# Connectors_and_Headers.net
KiCad netlist of a schematic drawn in Altium Designer
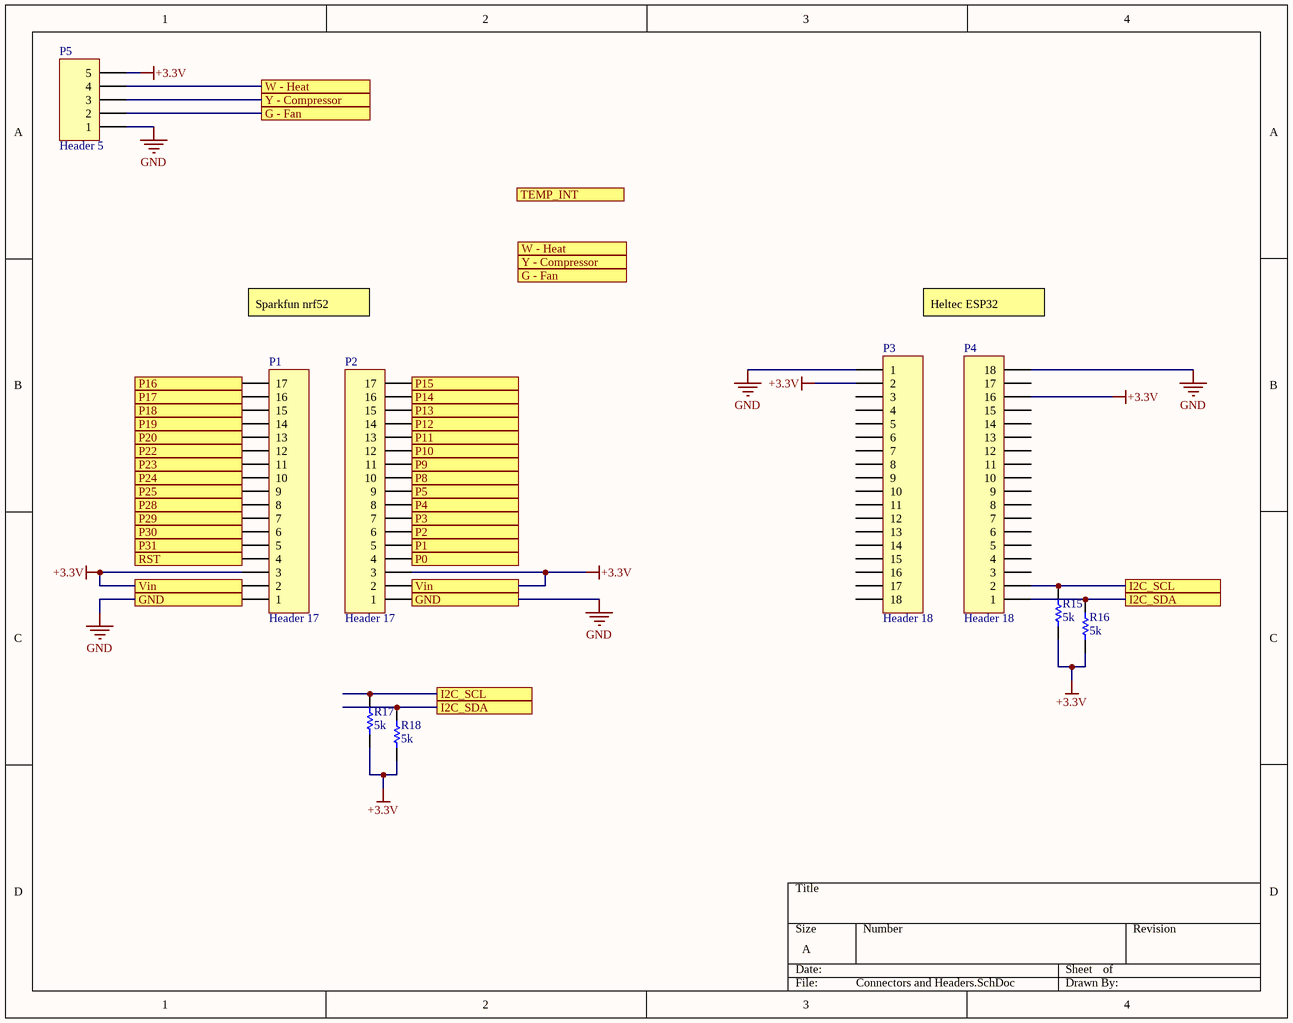
[diagram p0: Connectors and Headers.SchDoc]

(export (version "E")
  (design (tool "Eeschema 10.0.6"))
  (components
    (comp (ref "P1")
      (value "Header 17")
      (footprint "HDR1X17")
      (description "Header, 17-Pin")
      (fields (field (name "PUBLISHER") "Altium Limited"))
      (libsource (lib "Miscellaneous Connectors") (part "Header 17"))
    )
    (comp (ref "P2")
      (value "Header 17")
      (footprint "HDR1X17")
      (description "Header, 17-Pin")
      (fields (field (name "PUBLISHER") "Altium Limited"))
      (libsource (lib "") (part "Header 17_1"))
    )
    (comp (ref "P3")
      (value "Header 18")
      (footprint "HDR1X18")
      (description "Header, 18-Pin")
      (fields (field (name "PUBLISHER") "Altium Limited"))
      (libsource (lib "Miscellaneous Connectors") (part "Header 18"))
    )
    (comp (ref "P4")
      (value "Header 18")
      (footprint "HDR1X18")
      (description "Header, 18-Pin")
      (fields (field (name "PUBLISHER") "Altium Limited"))
      (libsource (lib "") (part "Header 18_1"))
    )
    (comp (ref "P5")
      (value "Header 5")
      (footprint "HDR1X5")
      (description "Header, 5-Pin")
      (fields (field (name "PUBLISHER") "Altium Limited"))
      (libsource (lib "Miscellaneous Connectors") (part "Header 5"))
    )
    (comp (ref "R15")
      (value "5k")
      (footprint "RESC2013X70X40LL20T20")
      (description "2012")
      (fields (field (name "PART NUMBER") "ERJ-6GEYJ471V") (field (name "MANUFACTURER") "Panasonic"))
      (libsource (lib "Altium Content Vault") (part "RES"))
    )
    (comp (ref "R16")
      (value "5k")
      (footprint "RESC2013X70X40LL20T20")
      (description "2012")
      (fields (field (name "PART NUMBER") "ERJ-6GEYJ471V") (field (name "MANUFACTURER") "Panasonic"))
      (libsource (lib "Altium Content Vault") (part "RES"))
    )
    (comp (ref "R17")
      (value "5k")
      (footprint "RESC2013X70X40LL20T20")
      (description "2012")
      (fields (field (name "PART NUMBER") "ERJ-6GEYJ471V") (field (name "MANUFACTURER") "Panasonic"))
      (libsource (lib "Altium Content Vault") (part "RES"))
    )
    (comp (ref "R18")
      (value "5k")
      (footprint "RESC2013X70X40LL20T20")
      (description "2012")
      (fields (field (name "PART NUMBER") "ERJ-6GEYJ471V") (field (name "MANUFACTURER") "Panasonic"))
      (libsource (lib "Altium Content Vault") (part "RES"))
    )
  )
  (nets
    (net (code "1") (name "+3.3V") (class "Default")
      (node (ref "P1") (pin "2") (pinfunction "2_2") (pintype "passive"))
      (node (ref "P1") (pin "3") (pinfunction "3_3") (pintype "passive"))
      (node (ref "P2") (pin "2") (pinfunction "2_2") (pintype "passive"))
      (node (ref "P2") (pin "3") (pinfunction "3_3") (pintype "passive"))
      (node (ref "P3") (pin "2") (pinfunction "2_2") (pintype "passive"))
      (node (ref "P4") (pin "16") (pinfunction "16_16") (pintype "passive"))
      (node (ref "P5") (pin "5") (pinfunction "5_5") (pintype "passive"))
      (node (ref "R15") (pin "1") (pinfunction "1_1") (pintype "passive"))
      (node (ref "R16") (pin "1") (pinfunction "1_1") (pintype "passive"))
      (node (ref "R17") (pin "1") (pinfunction "1_1") (pintype "passive"))
      (node (ref "R18") (pin "1") (pinfunction "1_1") (pintype "passive"))
    )
    (net (code "2") (name "/G - Fan") (class "Default")
      (node (ref "P5") (pin "2") (pinfunction "2_2") (pintype "passive"))
    )
    (net (code "3") (name "/I2C_SCL") (class "Default")
      (node (ref "P4") (pin "2") (pinfunction "2_2") (pintype "passive"))
      (node (ref "R15") (pin "2") (pinfunction "2_2") (pintype "passive"))
      (node (ref "R17") (pin "2") (pinfunction "2_2") (pintype "passive"))
    )
    (net (code "4") (name "/I2C_SDA") (class "Default")
      (node (ref "P4") (pin "1") (pinfunction "1_1") (pintype "passive"))
      (node (ref "R16") (pin "2") (pinfunction "2_2") (pintype "passive"))
      (node (ref "R18") (pin "2") (pinfunction "2_2") (pintype "passive"))
    )
    (net (code "5") (name "/P0") (class "Default")
      (node (ref "P2") (pin "4") (pinfunction "4_4") (pintype "passive"))
    )
    (net (code "6") (name "/P1") (class "Default")
      (node (ref "P2") (pin "5") (pinfunction "5_5") (pintype "passive"))
    )
    (net (code "7") (name "/P2") (class "Default")
      (node (ref "P2") (pin "6") (pinfunction "6_6") (pintype "passive"))
    )
    (net (code "8") (name "/P3") (class "Default")
      (node (ref "P2") (pin "7") (pinfunction "7_7") (pintype "passive"))
    )
    (net (code "9") (name "/P4") (class "Default")
      (node (ref "P2") (pin "8") (pinfunction "8_8") (pintype "passive"))
    )
    (net (code "10") (name "/P5") (class "Default")
      (node (ref "P2") (pin "9") (pinfunction "9_9") (pintype "passive"))
    )
    (net (code "11") (name "/P8") (class "Default")
      (node (ref "P2") (pin "10") (pinfunction "10_10") (pintype "passive"))
    )
    (net (code "12") (name "/P9") (class "Default")
      (node (ref "P2") (pin "11") (pinfunction "11_11") (pintype "passive"))
    )
    (net (code "13") (name "/P10") (class "Default")
      (node (ref "P2") (pin "12") (pinfunction "12_12") (pintype "passive"))
    )
    (net (code "14") (name "/P11") (class "Default")
      (node (ref "P2") (pin "13") (pinfunction "13_13") (pintype "passive"))
    )
    (net (code "15") (name "/P12") (class "Default")
      (node (ref "P2") (pin "14") (pinfunction "14_14") (pintype "passive"))
    )
    (net (code "16") (name "/P13") (class "Default")
      (node (ref "P2") (pin "15") (pinfunction "15_15") (pintype "passive"))
    )
    (net (code "17") (name "/P14") (class "Default")
      (node (ref "P2") (pin "16") (pinfunction "16_16") (pintype "passive"))
    )
    (net (code "18") (name "/P15") (class "Default")
      (node (ref "P2") (pin "17") (pinfunction "17_17") (pintype "passive"))
    )
    (net (code "19") (name "/P16") (class "Default")
      (node (ref "P1") (pin "17") (pinfunction "17_17") (pintype "passive"))
    )
    (net (code "20") (name "/P17") (class "Default")
      (node (ref "P1") (pin "16") (pinfunction "16_16") (pintype "passive"))
    )
    (net (code "21") (name "/P18") (class "Default")
      (node (ref "P1") (pin "15") (pinfunction "15_15") (pintype "passive"))
    )
    (net (code "22") (name "/P19") (class "Default")
      (node (ref "P1") (pin "14") (pinfunction "14_14") (pintype "passive"))
    )
    (net (code "23") (name "/P20") (class "Default")
      (node (ref "P1") (pin "13") (pinfunction "13_13") (pintype "passive"))
    )
    (net (code "24") (name "/P22") (class "Default")
      (node (ref "P1") (pin "12") (pinfunction "12_12") (pintype "passive"))
    )
    (net (code "25") (name "/P23") (class "Default")
      (node (ref "P1") (pin "11") (pinfunction "11_11") (pintype "passive"))
    )
    (net (code "26") (name "/P24") (class "Default")
      (node (ref "P1") (pin "10") (pinfunction "10_10") (pintype "passive"))
    )
    (net (code "27") (name "/P25") (class "Default")
      (node (ref "P1") (pin "9") (pinfunction "9_9") (pintype "passive"))
    )
    (net (code "28") (name "/P28") (class "Default")
      (node (ref "P1") (pin "8") (pinfunction "8_8") (pintype "passive"))
    )
    (net (code "29") (name "/P29") (class "Default")
      (node (ref "P1") (pin "7") (pinfunction "7_7") (pintype "passive"))
    )
    (net (code "30") (name "/P30") (class "Default")
      (node (ref "P1") (pin "6") (pinfunction "6_6") (pintype "passive"))
    )
    (net (code "31") (name "/P31") (class "Default")
      (node (ref "P1") (pin "5") (pinfunction "5_5") (pintype "passive"))
    )
    (net (code "32") (name "/RST") (class "Default")
      (node (ref "P1") (pin "4") (pinfunction "4_4") (pintype "passive"))
    )
    (net (code "34") (name "/W - Heat") (class "Default")
      (node (ref "P5") (pin "4") (pinfunction "4_4") (pintype "passive"))
    )
    (net (code "35") (name "/Y - Compressor") (class "Default")
      (node (ref "P5") (pin "3") (pinfunction "3_3") (pintype "passive"))
    )
    (net (code "36") (name "GND") (class "Default")
      (node (ref "P1") (pin "1") (pinfunction "1_1") (pintype "passive"))
      (node (ref "P2") (pin "1") (pinfunction "1_1") (pintype "passive"))
      (node (ref "P3") (pin "1") (pinfunction "1_1") (pintype "passive"))
      (node (ref "P4") (pin "18") (pinfunction "18_18") (pintype "passive"))
      (node (ref "P5") (pin "1") (pinfunction "1_1") (pintype "passive"))
    )
    (net (code "37") (name "unconnected-(P3-Pad3)") (class "Default")
      (node (ref "P3") (pin "3") (pinfunction "3_3") (pintype "passive"))
    )
    (net (code "38") (name "unconnected-(P3-Pad4)") (class "Default")
      (node (ref "P3") (pin "4") (pinfunction "4_4") (pintype "passive"))
    )
    (net (code "39") (name "unconnected-(P3-Pad5)") (class "Default")
      (node (ref "P3") (pin "5") (pinfunction "5_5") (pintype "passive"))
    )
    (net (code "40") (name "unconnected-(P3-Pad6)") (class "Default")
      (node (ref "P3") (pin "6") (pinfunction "6_6") (pintype "passive"))
    )
    (net (code "41") (name "unconnected-(P3-Pad7)") (class "Default")
      (node (ref "P3") (pin "7") (pinfunction "7_7") (pintype "passive"))
    )
    (net (code "42") (name "unconnected-(P3-Pad8)") (class "Default")
      (node (ref "P3") (pin "8") (pinfunction "8_8") (pintype "passive"))
    )
    (net (code "43") (name "unconnected-(P3-Pad9)") (class "Default")
      (node (ref "P3") (pin "9") (pinfunction "9_9") (pintype "passive"))
    )
    (net (code "44") (name "unconnected-(P3-Pad10)") (class "Default")
      (node (ref "P3") (pin "10") (pinfunction "10_10") (pintype "passive"))
    )
    (net (code "45") (name "unconnected-(P3-Pad11)") (class "Default")
      (node (ref "P3") (pin "11") (pinfunction "11_11") (pintype "passive"))
    )
    (net (code "46") (name "unconnected-(P3-Pad12)") (class "Default")
      (node (ref "P3") (pin "12") (pinfunction "12_12") (pintype "passive"))
    )
    (net (code "47") (name "unconnected-(P3-Pad13)") (class "Default")
      (node (ref "P3") (pin "13") (pinfunction "13_13") (pintype "passive"))
    )
    (net (code "48") (name "unconnected-(P3-Pad14)") (class "Default")
      (node (ref "P3") (pin "14") (pinfunction "14_14") (pintype "passive"))
    )
    (net (code "49") (name "unconnected-(P3-Pad15)") (class "Default")
      (node (ref "P3") (pin "15") (pinfunction "15_15") (pintype "passive"))
    )
    (net (code "50") (name "unconnected-(P3-Pad16)") (class "Default")
      (node (ref "P3") (pin "16") (pinfunction "16_16") (pintype "passive"))
    )
    (net (code "51") (name "unconnected-(P3-Pad17)") (class "Default")
      (node (ref "P3") (pin "17") (pinfunction "17_17") (pintype "passive"))
    )
    (net (code "52") (name "unconnected-(P3-Pad18)") (class "Default")
      (node (ref "P3") (pin "18") (pinfunction "18_18") (pintype "passive"))
    )
    (net (code "53") (name "unconnected-(P4-Pad3)") (class "Default")
      (node (ref "P4") (pin "3") (pinfunction "3_3") (pintype "passive"))
    )
    (net (code "54") (name "unconnected-(P4-Pad4)") (class "Default")
      (node (ref "P4") (pin "4") (pinfunction "4_4") (pintype "passive"))
    )
    (net (code "55") (name "unconnected-(P4-Pad5)") (class "Default")
      (node (ref "P4") (pin "5") (pinfunction "5_5") (pintype "passive"))
    )
    (net (code "56") (name "unconnected-(P4-Pad6)") (class "Default")
      (node (ref "P4") (pin "6") (pinfunction "6_6") (pintype "passive"))
    )
    (net (code "57") (name "unconnected-(P4-Pad7)") (class "Default")
      (node (ref "P4") (pin "7") (pinfunction "7_7") (pintype "passive"))
    )
    (net (code "58") (name "unconnected-(P4-Pad8)") (class "Default")
      (node (ref "P4") (pin "8") (pinfunction "8_8") (pintype "passive"))
    )
    (net (code "59") (name "unconnected-(P4-Pad9)") (class "Default")
      (node (ref "P4") (pin "9") (pinfunction "9_9") (pintype "passive"))
    )
    (net (code "60") (name "unconnected-(P4-Pad10)") (class "Default")
      (node (ref "P4") (pin "10") (pinfunction "10_10") (pintype "passive"))
    )
    (net (code "61") (name "unconnected-(P4-Pad11)") (class "Default")
      (node (ref "P4") (pin "11") (pinfunction "11_11") (pintype "passive"))
    )
    (net (code "62") (name "unconnected-(P4-Pad12)") (class "Default")
      (node (ref "P4") (pin "12") (pinfunction "12_12") (pintype "passive"))
    )
    (net (code "63") (name "unconnected-(P4-Pad13)") (class "Default")
      (node (ref "P4") (pin "13") (pinfunction "13_13") (pintype "passive"))
    )
    (net (code "64") (name "unconnected-(P4-Pad14)") (class "Default")
      (node (ref "P4") (pin "14") (pinfunction "14_14") (pintype "passive"))
    )
    (net (code "65") (name "unconnected-(P4-Pad15)") (class "Default")
      (node (ref "P4") (pin "15") (pinfunction "15_15") (pintype "passive"))
    )
    (net (code "66") (name "unconnected-(P4-Pad17)") (class "Default")
      (node (ref "P4") (pin "17") (pinfunction "17_17") (pintype "passive"))
    )
  )
)
